# BW1098FFC_Connector.net
KiCad netlist of a schematic drawn in Altium Designer
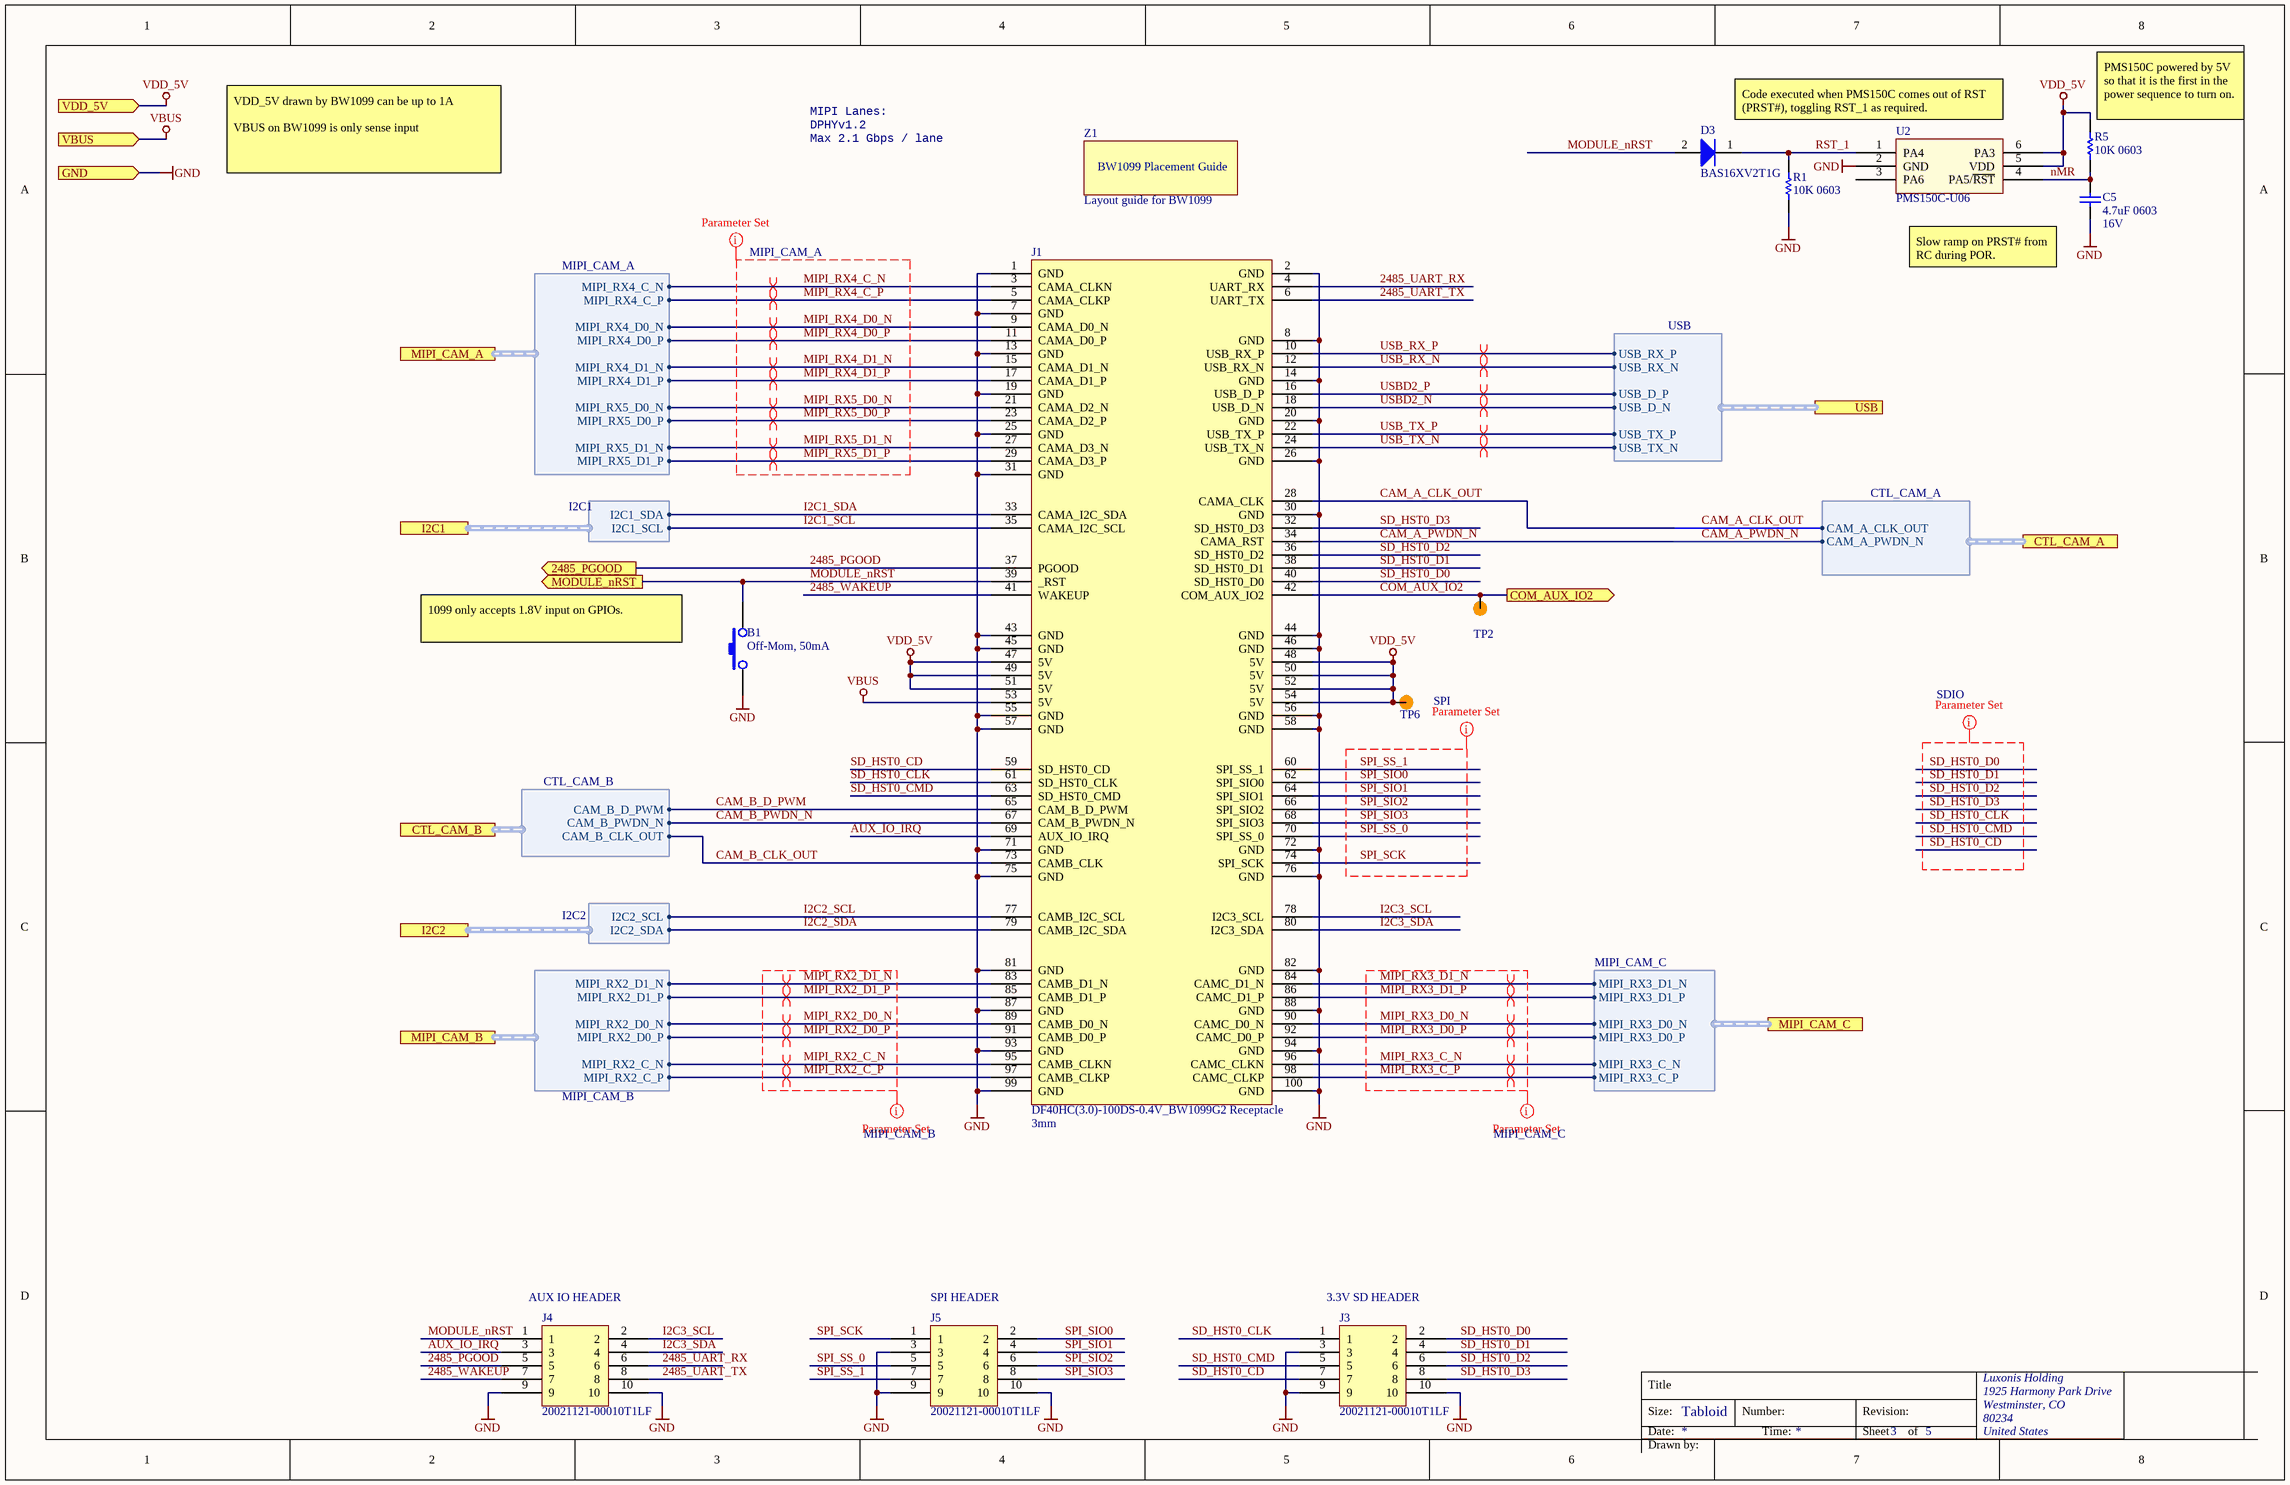
[diagram p0: BW1098FFC_Connector.SchDoc]

(export (version "E")
  (design (tool "Eeschema 10.0.6"))
  (components
    (comp (ref "B1")
      (value "Off-Mom, 50mA")
      (footprint "LuxonisMaster:DTSM-32N-V")
      (description "SWITCH TACTILE SMT 3.5mm * 6mm , brown 160gf")
      (libsource (lib "LuxonisMaster") (part "DTSM-32N-V"))
    )
    (comp (ref "C5")
      (value "4.7uF 0603")
      (footprint "CAP_Altium_Vault_Generic:CAPC0603(1608)100_N")
      (description "CAP CER 4.7UF 16V X5R 0603 10%")
      (fields (field (name "TOLERANCE") "10%") (field (name "VOLTAGE RATING") "16V"))
      (libsource (lib "LuxonisMaster") (part "GRM188R61C475KAAJD"))
    )
    (comp (ref "D3")
      (value "BAS16XV2T1G")
      (footprint "LuxonisMaster:BAS16XV2T1G")
      (description "DIODE GEN PURP 75V 200MA SOD523")
      (libsource (lib "LuxonisMaster") (part "BAS16XV2T1G"))
    )
    (comp (ref "J1")
      (value "DF40HC(3.0)-100DS-0.4V_BW1099G2 Receptacle")
      (footprint "LuxonisMaster:DF40HC-3.0-100DS-0.4V_minpad")
      (description "CONN RCPT 100POS 0.4MM SMD GOLD")
      (fields (field (name "MATED STACKING HEIGHT") "3mm"))
      (libsource (lib "LuxonisMaster") (part "DF40HC(3.0)-100DS-0.4V_BW1099_G2"))
    )
    (comp (ref "J3")
      (value "20021121-00010T1LF")
      (footprint "LuxonisMaster:20021121-00010T1LF")
      (description "CONN HEADER SMD 10POS 1.27MM")
      (libsource (lib "LuxonisMaster") (part "20021121-00010T1LF"))
    )
    (comp (ref "J4")
      (value "20021121-00010T1LF")
      (footprint "LuxonisMaster:20021121-00010T1LF")
      (description "CONN HEADER SMD 10POS 1.27MM")
      (libsource (lib "LuxonisMaster") (part "20021121-00010T1LF"))
    )
    (comp (ref "J5")
      (value "20021121-00010T1LF")
      (footprint "LuxonisMaster:20021121-00010T1LF")
      (description "CONN HEADER SMD 10POS 1.27MM")
      (libsource (lib "LuxonisMaster") (part "20021121-00010T1LF"))
    )
    (comp (ref "R1")
      (value "10K 0603")
      (footprint "RES_Altium_Vault_Generic:RESC0603(1608)_N")
      (description "RES SMD 10K OHM 1% 1/10W 0603")
      (fields (field (name "TOLERANCE") "1%"))
      (libsource (lib "LuxonisMaster") (part "RC0603FR-0710KL"))
    )
    (comp (ref "R5")
      (value "10K 0603")
      (footprint "RES_Altium_Vault_Generic:RESC0603(1608)_N")
      (description "RES SMD 10K OHM 1% 1/10W 0603")
      (fields (field (name "TOLERANCE") "1%"))
      (libsource (lib "LuxonisMaster") (part "RC0603FR-0710KL"))
    )
    (comp (ref "TP2")
      (value "TP100_200_NS")
      (footprint "LuxonisMaster:TP100_200_NS")
      (libsource (lib "LuxonisMaster") (part "TEST_POINT"))
    )
    (comp (ref "TP6")
      (value "TP100_200_NS")
      (footprint "LuxonisMaster:TP100_200_NS")
      (libsource (lib "LuxonisMaster") (part "TEST_POINT"))
    )
    (comp (ref "U2")
      (value "PMS150C-U06")
      (footprint "LuxonisMaster:PMS150C-U06")
      (description "Padauk 8bit OTP Type IO Controller - (SOT-23-6)")
      (libsource (lib "LuxonisMaster") (part "PMS150C-U06"))
    )
    (comp (ref "Z1")
      (value "Layout guide for BW1099")
      (footprint "LuxonisMaster:BW1099_Footprint")
      (description "MISC - Use for aligning BW1099 mount")
      (libsource (lib "LuxonisMaster") (part "BW1099_Footprint"))
    )
  )
  (nets
    (net (code "9") (name "/2485_PGOOD") (class "Default")
      (node (ref "J1") (pin "37") (pinfunction "PGOOD_37") (pintype "passive"))
      (node (ref "J4") (pin "5") (pinfunction "5_5") (pintype "passive"))
    )
    (net (code "10") (name "/2485_UART_RX") (class "Default")
      (node (ref "J1") (pin "4") (pinfunction "UART_RX_4") (pintype "passive"))
      (node (ref "J4") (pin "6") (pinfunction "6_6") (pintype "passive"))
    )
    (net (code "11") (name "/2485_UART_TX") (class "Default")
      (node (ref "J1") (pin "6") (pinfunction "UART_TX_6") (pintype "passive"))
      (node (ref "J4") (pin "8") (pinfunction "8_8") (pintype "passive"))
    )
    (net (code "12") (name "/2485_WAKEUP") (class "Default")
      (node (ref "J1") (pin "41") (pinfunction "WAKEUP_41") (pintype "passive"))
      (node (ref "J4") (pin "7") (pinfunction "7_7") (pintype "passive"))
    )
    (net (code "13") (name "/AUX_IO_IRQ") (class "Default")
      (node (ref "J1") (pin "69") (pinfunction "AUX_IO_IRQ_69") (pintype "passive"))
      (node (ref "J4") (pin "3") (pinfunction "3_3") (pintype "passive"))
    )
    (net (code "14") (name "/CAM_A_CLK_OUT") (class "Default")
      (node (ref "J1") (pin "28") (pinfunction "CAMA_CLK_28") (pintype "passive"))
    )
    (net (code "15") (name "/CAM_A_PWDN_N") (class "Default")
      (node (ref "J1") (pin "34") (pinfunction "CAMA_RST_34") (pintype "passive"))
    )
    (net (code "16") (name "/CAM_B_CLK_OUT") (class "Default")
      (node (ref "J1") (pin "73") (pinfunction "CAMB_CLK_73") (pintype "passive"))
    )
    (net (code "17") (name "/CAM_B_D_PWM") (class "Default")
      (node (ref "J1") (pin "65") (pinfunction "CAM_B_D_PWM_65") (pintype "passive"))
    )
    (net (code "18") (name "/CAM_B_PWDN_N") (class "Default")
      (node (ref "J1") (pin "67") (pinfunction "CAM_B_PWDN_N_67") (pintype "passive"))
    )
    (net (code "19") (name "/COM_AUX_IO2") (class "Default")
      (node (ref "J1") (pin "42") (pinfunction "COM_AUX_IO2_42") (pintype "passive"))
      (node (ref "TP2") (pin "1") (pintype "passive"))
    )
    (net (code "20") (name "/I2C1_SCL") (class "Default")
      (node (ref "J1") (pin "35") (pinfunction "CAMA_I2C_SCL_35") (pintype "passive"))
    )
    (net (code "21") (name "/I2C1_SDA") (class "Default")
      (node (ref "J1") (pin "33") (pinfunction "CAMA_I2C_SDA_33") (pintype "passive"))
    )
    (net (code "22") (name "/I2C2_SCL") (class "Default")
      (node (ref "J1") (pin "77") (pinfunction "CAMB_I2C_SCL_77") (pintype "passive"))
    )
    (net (code "23") (name "/I2C2_SDA") (class "Default")
      (node (ref "J1") (pin "79") (pinfunction "CAMB_I2C_SDA_79") (pintype "passive"))
    )
    (net (code "24") (name "/I2C3_SCL") (class "Default")
      (node (ref "J1") (pin "78") (pinfunction "I2C3_SCL_78") (pintype "passive"))
      (node (ref "J4") (pin "2") (pinfunction "2_2") (pintype "passive"))
    )
    (net (code "25") (name "/I2C3_SDA") (class "Default")
      (node (ref "J1") (pin "80") (pinfunction "I2C3_SDA_80") (pintype "passive"))
      (node (ref "J4") (pin "4") (pinfunction "4_4") (pintype "passive"))
    )
    (net (code "26") (name "/MIPI_RX2_C_N") (class "Default")
      (node (ref "J1") (pin "95") (pinfunction "CAMB_CLKN_95") (pintype "passive"))
    )
    (net (code "27") (name "/MIPI_RX2_C_P") (class "Default")
      (node (ref "J1") (pin "97") (pinfunction "CAMB_CLKP_97") (pintype "passive"))
    )
    (net (code "28") (name "/MIPI_RX2_D0_N") (class "Default")
      (node (ref "J1") (pin "89") (pinfunction "CAMB_D0_N_89") (pintype "passive"))
    )
    (net (code "29") (name "/MIPI_RX2_D0_P") (class "Default")
      (node (ref "J1") (pin "91") (pinfunction "CAMB_D0_P_91") (pintype "passive"))
    )
    (net (code "30") (name "/MIPI_RX2_D1_N") (class "Default")
      (node (ref "J1") (pin "83") (pinfunction "CAMB_D1_N_83") (pintype "passive"))
    )
    (net (code "31") (name "/MIPI_RX2_D1_P") (class "Default")
      (node (ref "J1") (pin "85") (pinfunction "CAMB_D1_P_85") (pintype "passive"))
    )
    (net (code "32") (name "/MIPI_RX3_C_N") (class "Default")
      (node (ref "J1") (pin "96") (pinfunction "CAMC_CLKN_96") (pintype "passive"))
    )
    (net (code "33") (name "/MIPI_RX3_C_P") (class "Default")
      (node (ref "J1") (pin "98") (pinfunction "CAMC_CLKP_98") (pintype "passive"))
    )
    (net (code "34") (name "/MIPI_RX3_D0_N") (class "Default")
      (node (ref "J1") (pin "90") (pinfunction "CAMC_D0_N_90") (pintype "passive"))
    )
    (net (code "35") (name "/MIPI_RX3_D0_P") (class "Default")
      (node (ref "J1") (pin "92") (pinfunction "CAMC_D0_P_92") (pintype "passive"))
    )
    (net (code "36") (name "/MIPI_RX3_D1_N") (class "Default")
      (node (ref "J1") (pin "84") (pinfunction "CAMC_D1_N_84") (pintype "passive"))
    )
    (net (code "37") (name "/MIPI_RX3_D1_P") (class "Default")
      (node (ref "J1") (pin "86") (pinfunction "CAMC_D1_P_86") (pintype "passive"))
    )
    (net (code "38") (name "/MIPI_RX4_C_N") (class "Default")
      (node (ref "J1") (pin "3") (pinfunction "CAMA_CLKN_3") (pintype "passive"))
    )
    (net (code "39") (name "/MIPI_RX4_C_P") (class "Default")
      (node (ref "J1") (pin "5") (pinfunction "CAMA_CLKP_5") (pintype "passive"))
    )
    (net (code "40") (name "/MIPI_RX4_D0_N") (class "Default")
      (node (ref "J1") (pin "9") (pinfunction "CAMA_D0_N_9") (pintype "passive"))
    )
    (net (code "41") (name "/MIPI_RX4_D0_P") (class "Default")
      (node (ref "J1") (pin "11") (pinfunction "CAMA_D0_P_11") (pintype "passive"))
    )
    (net (code "42") (name "/MIPI_RX4_D1_N") (class "Default")
      (node (ref "J1") (pin "15") (pinfunction "CAMA_D1_N_15") (pintype "passive"))
    )
    (net (code "43") (name "/MIPI_RX4_D1_P") (class "Default")
      (node (ref "J1") (pin "17") (pinfunction "CAMA_D1_P_17") (pintype "passive"))
    )
    (net (code "44") (name "/MIPI_RX5_D0_N") (class "Default")
      (node (ref "J1") (pin "21") (pinfunction "CAMA_D2_N_21") (pintype "passive"))
    )
    (net (code "45") (name "/MIPI_RX5_D0_P") (class "Default")
      (node (ref "J1") (pin "23") (pinfunction "CAMA_D2_P_23") (pintype "passive"))
    )
    (net (code "46") (name "/MIPI_RX5_D1_N") (class "Default")
      (node (ref "J1") (pin "27") (pinfunction "CAMA_D3_N_27") (pintype "passive"))
    )
    (net (code "47") (name "/MIPI_RX5_D1_P") (class "Default")
      (node (ref "J1") (pin "29") (pinfunction "CAMA_D3_P_29") (pintype "passive"))
    )
    (net (code "48") (name "/MODULE_nRST") (class "Default")
      (node (ref "B1") (pin "2") (pinfunction "2_2") (pintype "passive"))
      (node (ref "D3") (pin "2") (pinfunction "A_2") (pintype "passive"))
      (node (ref "J1") (pin "39") (pinfunction "_RST_39") (pintype "passive"))
      (node (ref "J4") (pin "1") (pinfunction "1_1") (pintype "passive"))
    )
    (net (code "49") (name "/RST_1") (class "Default")
      (node (ref "D3") (pin "1") (pinfunction "K_1") (pintype "passive"))
      (node (ref "R1") (pin "2") (pinfunction "2_2") (pintype "passive"))
      (node (ref "U2") (pin "1") (pinfunction "PA4_1") (pintype "passive"))
    )
    (net (code "50") (name "/SD_HST0_CD") (class "Default")
      (node (ref "J1") (pin "59") (pinfunction "SD_HST0_CD_59") (pintype "passive"))
      (node (ref "J3") (pin "7") (pinfunction "7_7") (pintype "passive"))
    )
    (net (code "51") (name "/SD_HST0_CLK") (class "Default")
      (node (ref "J1") (pin "61") (pinfunction "SD_HST0_CLK_61") (pintype "passive"))
      (node (ref "J3") (pin "1") (pinfunction "1_1") (pintype "passive"))
    )
    (net (code "52") (name "/SD_HST0_CMD") (class "Default")
      (node (ref "J1") (pin "63") (pinfunction "SD_HST0_CMD_63") (pintype "passive"))
      (node (ref "J3") (pin "5") (pinfunction "5_5") (pintype "passive"))
    )
    (net (code "53") (name "/SD_HST0_D0") (class "Default")
      (node (ref "J1") (pin "40") (pinfunction "SD_HST0_D0_40") (pintype "passive"))
      (node (ref "J3") (pin "2") (pinfunction "2_2") (pintype "passive"))
    )
    (net (code "54") (name "/SD_HST0_D1") (class "Default")
      (node (ref "J1") (pin "38") (pinfunction "SD_HST0_D1_38") (pintype "passive"))
      (node (ref "J3") (pin "4") (pinfunction "4_4") (pintype "passive"))
    )
    (net (code "55") (name "/SD_HST0_D2") (class "Default")
      (node (ref "J1") (pin "36") (pinfunction "SD_HST0_D2_36") (pintype "passive"))
      (node (ref "J3") (pin "6") (pinfunction "6_6") (pintype "passive"))
    )
    (net (code "56") (name "/SD_HST0_D3") (class "Default")
      (node (ref "J1") (pin "32") (pinfunction "SD_HST0_D3_32") (pintype "passive"))
      (node (ref "J3") (pin "8") (pinfunction "8_8") (pintype "passive"))
    )
    (net (code "57") (name "/SPI_SCK") (class "Default")
      (node (ref "J1") (pin "74") (pinfunction "SPI_SCK_74") (pintype "passive"))
      (node (ref "J5") (pin "1") (pinfunction "1_1") (pintype "passive"))
    )
    (net (code "58") (name "/SPI_SIO0") (class "Default")
      (node (ref "J1") (pin "62") (pinfunction "SPI_SIO0_62") (pintype "passive"))
      (node (ref "J5") (pin "2") (pinfunction "2_2") (pintype "passive"))
    )
    (net (code "59") (name "/SPI_SIO1") (class "Default")
      (node (ref "J1") (pin "64") (pinfunction "SPI_SIO1_64") (pintype "passive"))
      (node (ref "J5") (pin "4") (pinfunction "4_4") (pintype "passive"))
    )
    (net (code "60") (name "/SPI_SIO2") (class "Default")
      (node (ref "J1") (pin "66") (pinfunction "SPI_SIO2_66") (pintype "passive"))
      (node (ref "J5") (pin "6") (pinfunction "6_6") (pintype "passive"))
    )
    (net (code "61") (name "/SPI_SIO3") (class "Default")
      (node (ref "J1") (pin "68") (pinfunction "SPI_SIO3_68") (pintype "passive"))
      (node (ref "J5") (pin "8") (pinfunction "8_8") (pintype "passive"))
    )
    (net (code "62") (name "/SPI_SS_0") (class "Default")
      (node (ref "J1") (pin "70") (pinfunction "SPI_SS_0_70") (pintype "passive"))
      (node (ref "J5") (pin "5") (pinfunction "5_5") (pintype "passive"))
    )
    (net (code "63") (name "/SPI_SS_1") (class "Default")
      (node (ref "J1") (pin "60") (pinfunction "SPI_SS_1_60") (pintype "passive"))
      (node (ref "J5") (pin "7") (pinfunction "7_7") (pintype "passive"))
    )
    (net (code "64") (name "/USBD2_N") (class "Default")
      (node (ref "J1") (pin "18") (pinfunction "USB_D_N_18") (pintype "passive"))
    )
    (net (code "65") (name "/USBD2_P") (class "Default")
      (node (ref "J1") (pin "16") (pinfunction "USB_D_P_16") (pintype "passive"))
    )
    (net (code "66") (name "/USB_RX_N") (class "Default")
      (node (ref "J1") (pin "12") (pinfunction "USB_RX_N_12") (pintype "passive"))
    )
    (net (code "67") (name "/USB_RX_P") (class "Default")
      (node (ref "J1") (pin "10") (pinfunction "USB_RX_P_10") (pintype "passive"))
    )
    (net (code "68") (name "/USB_TX_N") (class "Default")
      (node (ref "J1") (pin "24") (pinfunction "USB_TX_N_24") (pintype "passive"))
    )
    (net (code "69") (name "/USB_TX_P") (class "Default")
      (node (ref "J1") (pin "22") (pinfunction "USB_TX_P_22") (pintype "passive"))
    )
    (net (code "70") (name "/nMR") (class "Default")
      (node (ref "C5") (pin "2") (pinfunction "2_2") (pintype "passive"))
      (node (ref "R5") (pin "1") (pinfunction "1_1") (pintype "passive"))
      (node (ref "U2") (pin "4") (pinfunction "PA5/~{RST}_4") (pintype "passive"))
    )
    (net (code "79") (name "GND") (class "Default")
      (node (ref "B1") (pin "1") (pinfunction "1_1") (pintype "passive"))
      (node (ref "C5") (pin "1") (pinfunction "1_1") (pintype "passive"))
      (node (ref "J1") (pin "1") (pinfunction "GND_1") (pintype "passive"))
      (node (ref "J1") (pin "100") (pinfunction "GND_100") (pintype "passive"))
      (node (ref "J1") (pin "13") (pinfunction "GND_13") (pintype "passive"))
      (node (ref "J1") (pin "14") (pinfunction "GND_14") (pintype "passive"))
      (node (ref "J1") (pin "19") (pinfunction "GND_19") (pintype "passive"))
      (node (ref "J1") (pin "2") (pinfunction "GND_2") (pintype "passive"))
      (node (ref "J1") (pin "20") (pinfunction "GND_20") (pintype "passive"))
      (node (ref "J1") (pin "25") (pinfunction "GND_25") (pintype "passive"))
      (node (ref "J1") (pin "26") (pinfunction "GND_26") (pintype "passive"))
      (node (ref "J1") (pin "30") (pinfunction "GND_30") (pintype "passive"))
      (node (ref "J1") (pin "31") (pinfunction "GND_31") (pintype "passive"))
      (node (ref "J1") (pin "43") (pinfunction "GND_43") (pintype "passive"))
      (node (ref "J1") (pin "44") (pinfunction "GND_44") (pintype "passive"))
      (node (ref "J1") (pin "45") (pinfunction "GND_45") (pintype "passive"))
      (node (ref "J1") (pin "46") (pinfunction "GND_46") (pintype "passive"))
      (node (ref "J1") (pin "55") (pinfunction "GND_55") (pintype "passive"))
      (node (ref "J1") (pin "56") (pinfunction "GND_56") (pintype "passive"))
      (node (ref "J1") (pin "57") (pinfunction "GND_57") (pintype "passive"))
      (node (ref "J1") (pin "58") (pinfunction "GND_58") (pintype "passive"))
      (node (ref "J1") (pin "7") (pinfunction "GND_7") (pintype "passive"))
      (node (ref "J1") (pin "71") (pinfunction "GND_71") (pintype "passive"))
      (node (ref "J1") (pin "72") (pinfunction "GND_72") (pintype "passive"))
      (node (ref "J1") (pin "75") (pinfunction "GND_75") (pintype "passive"))
      (node (ref "J1") (pin "76") (pinfunction "GND_76") (pintype "passive"))
      (node (ref "J1") (pin "8") (pinfunction "GND_8") (pintype "passive"))
      (node (ref "J1") (pin "81") (pinfunction "GND_81") (pintype "passive"))
      (node (ref "J1") (pin "82") (pinfunction "GND_82") (pintype "passive"))
      (node (ref "J1") (pin "87") (pinfunction "GND_87") (pintype "passive"))
      (node (ref "J1") (pin "88") (pinfunction "GND_88") (pintype "passive"))
      (node (ref "J1") (pin "93") (pinfunction "GND_93") (pintype "passive"))
      (node (ref "J1") (pin "94") (pinfunction "GND_94") (pintype "passive"))
      (node (ref "J1") (pin "99") (pinfunction "GND_99") (pintype "passive"))
      (node (ref "J3") (pin "10") (pinfunction "10_10") (pintype "passive"))
      (node (ref "J3") (pin "3") (pinfunction "3_3") (pintype "passive"))
      (node (ref "J3") (pin "9") (pinfunction "9_9") (pintype "passive"))
      (node (ref "J4") (pin "10") (pinfunction "10_10") (pintype "passive"))
      (node (ref "J4") (pin "9") (pinfunction "9_9") (pintype "passive"))
      (node (ref "J5") (pin "10") (pinfunction "10_10") (pintype "passive"))
      (node (ref "J5") (pin "3") (pinfunction "3_3") (pintype "passive"))
      (node (ref "J5") (pin "9") (pinfunction "9_9") (pintype "passive"))
      (node (ref "R1") (pin "1") (pinfunction "1_1") (pintype "passive"))
      (node (ref "U2") (pin "2") (pinfunction "GND_2") (pintype "passive"))
    )
    (net (code "80") (name "VBUS") (class "Default")
      (node (ref "J1") (pin "53") (pinfunction "5V_53") (pintype "passive"))
    )
    (net (code "81") (name "VDD_5V") (class "Default")
      (node (ref "J1") (pin "47") (pinfunction "5V_47") (pintype "passive"))
      (node (ref "J1") (pin "48") (pinfunction "5V_48") (pintype "passive"))
      (node (ref "J1") (pin "49") (pinfunction "5V_49") (pintype "passive"))
      (node (ref "J1") (pin "50") (pinfunction "5V_50") (pintype "passive"))
      (node (ref "J1") (pin "51") (pinfunction "5V_51") (pintype "passive"))
      (node (ref "J1") (pin "52") (pinfunction "5V_52") (pintype "passive"))
      (node (ref "J1") (pin "54") (pinfunction "5V_54") (pintype "passive"))
      (node (ref "R5") (pin "2") (pinfunction "2_2") (pintype "passive"))
      (node (ref "TP6") (pin "1") (pintype "passive"))
      (node (ref "U2") (pin "5") (pinfunction "VDD_5") (pintype "passive"))
      (node (ref "U2") (pin "6") (pinfunction "PA3_6") (pintype "passive"))
    )
    (net (code "82") (name "unconnected-(U2-PA6-Pad3)") (class "Default")
      (node (ref "U2") (pin "3") (pinfunction "PA6_3") (pintype "passive"))
    )
  )
)
